# TPaD_Tablet_v1.net
KiCad netlist of a schematic drawn in EAGLE
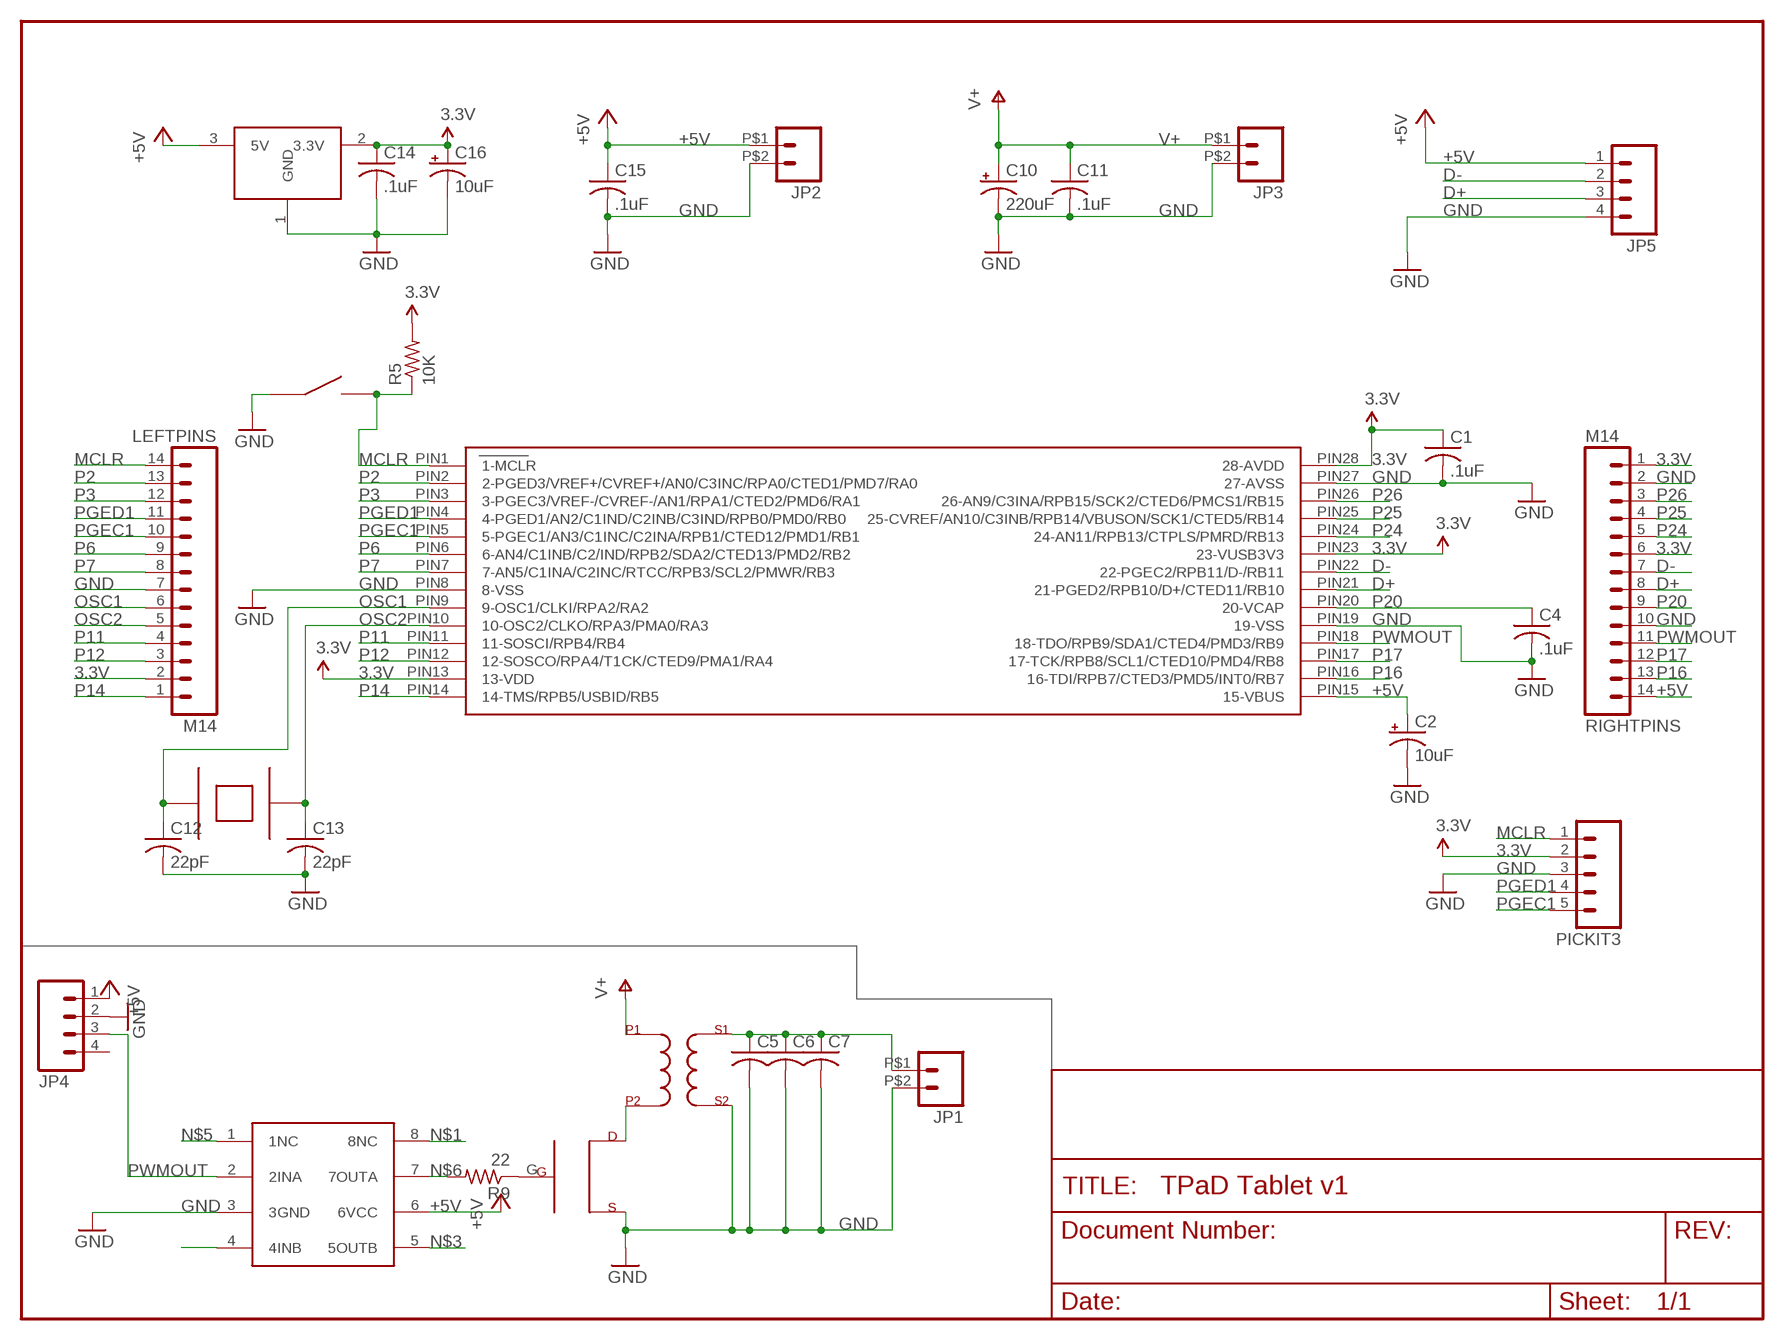
[diagram p0: schematic, sheet 1]

(export (version "E")
  (design (tool "Eeschema 10.0.6"))
  (components
    (comp (ref "C1")
      (value ".1uF")
      (footprint "eagle-import:C050-035X075")
      (libsource (lib "eagle-import") (part "C-US050-035X075"))
    )
    (comp (ref "C2")
      (value "10uF")
      (footprint "eagle-import:E2-5")
      (libsource (lib "eagle-import") (part "CPOL-USE2-5"))
    )
    (comp (ref "C4")
      (value ".1uF")
      (footprint "eagle-import:C050-035X075")
      (libsource (lib "eagle-import") (part "C-US050-035X075"))
    )
    (comp (ref "C5")
      (value "C-US050-035X075")
      (footprint "eagle-import:C050-035X075")
      (libsource (lib "eagle-import") (part "C-US050-035X075"))
    )
    (comp (ref "C6")
      (value "C-US050-035X075")
      (footprint "eagle-import:C050-035X075")
      (libsource (lib "eagle-import") (part "C-US050-035X075"))
    )
    (comp (ref "C7")
      (value "C-US050-035X075")
      (footprint "eagle-import:C050-035X075")
      (libsource (lib "eagle-import") (part "C-US050-035X075"))
    )
    (comp (ref "C10")
      (value "220uF")
      (footprint "eagle-import:TT2D6")
      (libsource (lib "eagle-import") (part "CPOL-USTT2D6"))
    )
    (comp (ref "C11")
      (value ".1uF")
      (footprint "eagle-import:C050-035X075")
      (libsource (lib "eagle-import") (part "C-US050-035X075"))
    )
    (comp (ref "C12")
      (value "22pF")
      (footprint "eagle-import:C025-024X044")
      (libsource (lib "eagle-import") (part "C-US025-024X044"))
    )
    (comp (ref "C13")
      (value "22pF")
      (footprint "eagle-import:C025-024X044")
      (libsource (lib "eagle-import") (part "C-US025-024X044"))
    )
    (comp (ref "C14")
      (value ".1uF")
      (footprint "eagle-import:C050-035X075")
      (libsource (lib "eagle-import") (part "C-US050-035X075"))
    )
    (comp (ref "C15")
      (value ".1uF")
      (footprint "eagle-import:C050-035X075")
      (libsource (lib "eagle-import") (part "C-US050-035X075"))
    )
    (comp (ref "C16")
      (value "10uF")
      (footprint "eagle-import:E2-5")
      (libsource (lib "eagle-import") (part "CPOL-USE2-5"))
    )
    (comp (ref "JP1")
      (value "M02PTH2")
      (footprint "eagle-import:1X02_BIG")
      (libsource (lib "eagle-import") (part "M02PTH2"))
    )
    (comp (ref "JP2")
      (value "M02PTH2")
      (footprint "eagle-import:1X02_BIG")
      (libsource (lib "eagle-import") (part "M02PTH2"))
    )
    (comp (ref "JP3")
      (value "M02PTH2")
      (footprint "eagle-import:1X02_BIG")
      (libsource (lib "eagle-import") (part "M02PTH2"))
    )
    (comp (ref "JP4")
      (value "M04PTH")
      (footprint "eagle-import:1X04")
      (libsource (lib "eagle-import") (part "M04PTH"))
    )
    (comp (ref "JP5")
      (value "M04PTH")
      (footprint "eagle-import:1X04")
      (libsource (lib "eagle-import") (part "SparkFun-Connectors_M04PTH"))
    )
    (comp (ref "LEFTPINS")
      (value "M14")
      (footprint "eagle-import:1X14")
      (libsource (lib "eagle-import") (part "M14"))
    )
    (comp (ref "PICKIT3")
      (value "M05PTH")
      (footprint "eagle-import:1X05")
      (libsource (lib "eagle-import") (part "M05PTH"))
    )
    (comp (ref "R5")
      (value "10K")
      (footprint "eagle-import:0207_10")
      (libsource (lib "eagle-import") (part "R-US_0207/10"))
    )
    (comp (ref "R9")
      (value "22")
      (footprint "eagle-import:0207_10")
      (libsource (lib "eagle-import") (part "R-US_0207/10"))
    )
    (comp (ref "RIGHTPINS")
      (value "M14")
      (footprint "eagle-import:1X14")
      (libsource (lib "eagle-import") (part "M14"))
    )
    (comp (ref "U$1")
      (value "PIC32MX250F128B")
      (footprint "eagle-import:DIP28-PIC32")
      (libsource (lib "eagle-import") (part "PIC32MX250F128B"))
    )
    (comp (ref "U$3")
      (value "GATEDRIVER")
      (footprint "eagle-import:DIL-08")
      (libsource (lib "eagle-import") (part "GATEDRIVER"))
    )
    (comp (ref "U$4")
      (value "TRANSFORMER")
      (footprint "eagle-import:TRANSFORMER")
      (libsource (lib "eagle-import") (part "TRANSFORMER"))
    )
    (comp (ref "U$5")
      (value "TPAD_IRF520N")
      (footprint "eagle-import:TPAD_TO220")
      (libsource (lib "eagle-import") (part "TPAD_IRF520N"))
    )
    (comp (ref "U$6")
      (value "LD33V")
      (footprint "eagle-import:SOT223")
      (libsource (lib "eagle-import") (part "LD33V"))
    )
    (comp (ref "U$7")
      (value "OSCILLATOR")
      (footprint "eagle-import:OSC")
      (libsource (lib "eagle-import") (part "OSCILLATOR"))
    )
    (comp (ref "U$8")
      (value "SWITCH")
      (footprint "eagle-import:OSC")
      (libsource (lib "eagle-import") (part "SWITCH"))
    )
  )
  (nets
    (net (code "1") (name "+5V") (class "Default")
      (node (ref "C15") (pin "1") (pinfunction "1_1") (pintype "passive"))
      (node (ref "C2") (pin "+") (pinfunction "+_+") (pintype "passive"))
      (node (ref "JP2") (pin "P$1") (pinfunction "1_P$1") (pintype "passive"))
      (node (ref "JP4") (pin "1") (pinfunction "1_1") (pintype "passive"))
      (node (ref "JP5") (pin "1") (pinfunction "1_1") (pintype "passive"))
      (node (ref "RIGHTPINS") (pin "14") (pinfunction "14_14") (pintype "passive"))
      (node (ref "U$1") (pin "PIN15") (pinfunction "15-VBUS_PIN15") (pintype "bidirectional"))
      (node (ref "U$3") (pin "6") (pinfunction "6VCC_6") (pintype "bidirectional"))
      (node (ref "U$6") (pin "3") (pinfunction "5V_3") (pintype "bidirectional"))
    )
    (net (code "2") (name "/D+") (class "Default")
      (node (ref "JP5") (pin "3") (pinfunction "3_3") (pintype "passive"))
      (node (ref "RIGHTPINS") (pin "8") (pinfunction "8_8") (pintype "passive"))
      (node (ref "U$1") (pin "PIN21") (pinfunction "21-PGED2/RPB10/D+/CTED11/RB10_PIN21") (pintype "bidirectional"))
    )
    (net (code "3") (name "/D-") (class "Default")
      (node (ref "JP5") (pin "2") (pinfunction "2_2") (pintype "passive"))
      (node (ref "RIGHTPINS") (pin "7") (pinfunction "7_7") (pintype "passive"))
      (node (ref "U$1") (pin "PIN22") (pinfunction "22-PGEC2/RPB11/D-/RB11_PIN22") (pintype "bidirectional"))
    )
    (net (code "4") (name "/MCLR") (class "Default")
      (node (ref "LEFTPINS") (pin "14") (pinfunction "14_14") (pintype "passive"))
      (node (ref "PICKIT3") (pin "1") (pinfunction "1_1") (pintype "passive"))
      (node (ref "R5") (pin "1") (pinfunction "1_1") (pintype "passive"))
      (node (ref "U$1") (pin "PIN1") (pinfunction "1-MCLR_PIN1") (pintype "bidirectional"))
      (node (ref "U$8") (pin "P$3") (pinfunction "P$2_P$3") (pintype "bidirectional"))
    )
    (net (code "5") (name "/N$1") (class "Default")
      (node (ref "U$3") (pin "8") (pinfunction "8NC_8") (pintype "bidirectional"))
    )
    (net (code "6") (name "/N$3") (class "Default")
      (node (ref "U$3") (pin "5") (pinfunction "5OUTB_5") (pintype "bidirectional"))
    )
    (net (code "7") (name "/N$5") (class "Default")
      (node (ref "U$3") (pin "1") (pinfunction "1NC_1") (pintype "bidirectional"))
    )
    (net (code "8") (name "/N$6") (class "Default")
      (node (ref "R9") (pin "2") (pinfunction "2_2") (pintype "passive"))
      (node (ref "U$3") (pin "7") (pinfunction "7OUTA_7") (pintype "bidirectional"))
    )
    (net (code "9") (name "/OSC1") (class "Default")
      (node (ref "C12") (pin "1") (pinfunction "1_1") (pintype "passive"))
      (node (ref "LEFTPINS") (pin "6") (pinfunction "6_6") (pintype "passive"))
      (node (ref "U$1") (pin "PIN9") (pinfunction "9-OSC1/CLKI/RPA2/RA2_PIN9") (pintype "bidirectional"))
      (node (ref "U$7") (pin "P$3") (pinfunction "P$2_P$3") (pintype "bidirectional"))
    )
    (net (code "10") (name "/OSC2") (class "Default")
      (node (ref "C13") (pin "1") (pinfunction "1_1") (pintype "passive"))
      (node (ref "LEFTPINS") (pin "5") (pinfunction "5_5") (pintype "passive"))
      (node (ref "U$1") (pin "PIN10") (pinfunction "10-OSC2/CLKO/RPA3/PMA0/RA3_PIN10") (pintype "bidirectional"))
      (node (ref "U$7") (pin "P$1") (pinfunction "P$1_P$1") (pintype "bidirectional"))
    )
    (net (code "11") (name "/P2") (class "Default")
      (node (ref "LEFTPINS") (pin "13") (pinfunction "13_13") (pintype "passive"))
      (node (ref "U$1") (pin "PIN2") (pinfunction "2-PGED3/VREF+/CVREF+/AN0/C3INC/RPA0/CTED1/PMD7/RA0_PIN2") (pintype "bidirectional"))
    )
    (net (code "12") (name "/P3") (class "Default")
      (node (ref "LEFTPINS") (pin "12") (pinfunction "12_12") (pintype "passive"))
      (node (ref "U$1") (pin "PIN3") (pinfunction "3-PGEC3/VREF-/CVREF-/AN1/RPA1/CTED2/PMD6/RA1_PIN3") (pintype "bidirectional"))
    )
    (net (code "13") (name "/P6") (class "Default")
      (node (ref "LEFTPINS") (pin "9") (pinfunction "9_9") (pintype "passive"))
      (node (ref "U$1") (pin "PIN6") (pinfunction "6-AN4/C1INB/C2/IND/RPB2/SDA2/CTED13/PMD2/RB2_PIN6") (pintype "bidirectional"))
    )
    (net (code "14") (name "/P7") (class "Default")
      (node (ref "LEFTPINS") (pin "8") (pinfunction "8_8") (pintype "passive"))
      (node (ref "U$1") (pin "PIN7") (pinfunction "7-AN5/C1INA/C2INC/RTCC/RPB3/SCL2/PMWR/RB3_PIN7") (pintype "bidirectional"))
    )
    (net (code "15") (name "/P11") (class "Default")
      (node (ref "LEFTPINS") (pin "4") (pinfunction "4_4") (pintype "passive"))
      (node (ref "U$1") (pin "PIN11") (pinfunction "11-SOSCI/RPB4/RB4_PIN11") (pintype "bidirectional"))
    )
    (net (code "16") (name "/P12") (class "Default")
      (node (ref "LEFTPINS") (pin "3") (pinfunction "3_3") (pintype "passive"))
      (node (ref "U$1") (pin "PIN12") (pinfunction "12-SOSCO/RPA4/T1CK/CTED9/PMA1/RA4_PIN12") (pintype "bidirectional"))
    )
    (net (code "17") (name "/P14") (class "Default")
      (node (ref "LEFTPINS") (pin "1") (pinfunction "1_1") (pintype "passive"))
      (node (ref "U$1") (pin "PIN14") (pinfunction "14-TMS/RPB5/USBID/RB5_PIN14") (pintype "bidirectional"))
    )
    (net (code "18") (name "/P16") (class "Default")
      (node (ref "RIGHTPINS") (pin "13") (pinfunction "13_13") (pintype "passive"))
      (node (ref "U$1") (pin "PIN16") (pinfunction "16-TDI/RPB7/CTED3/PMD5/INT0/RB7_PIN16") (pintype "bidirectional"))
    )
    (net (code "19") (name "/P17") (class "Default")
      (node (ref "RIGHTPINS") (pin "12") (pinfunction "12_12") (pintype "passive"))
      (node (ref "U$1") (pin "PIN17") (pinfunction "17-TCK/RPB8/SCL1/CTED10/PMD4/RB8_PIN17") (pintype "bidirectional"))
    )
    (net (code "20") (name "/P20") (class "Default")
      (node (ref "C4") (pin "1") (pinfunction "1_1") (pintype "passive"))
      (node (ref "RIGHTPINS") (pin "9") (pinfunction "9_9") (pintype "passive"))
      (node (ref "U$1") (pin "PIN20") (pinfunction "20-VCAP_PIN20") (pintype "bidirectional"))
    )
    (net (code "21") (name "/P24") (class "Default")
      (node (ref "RIGHTPINS") (pin "5") (pinfunction "5_5") (pintype "passive"))
      (node (ref "U$1") (pin "PIN24") (pinfunction "24-AN11/RPB13/CTPLS/PMRD/RB13_PIN24") (pintype "bidirectional"))
    )
    (net (code "22") (name "/P25") (class "Default")
      (node (ref "RIGHTPINS") (pin "4") (pinfunction "4_4") (pintype "passive"))
      (node (ref "U$1") (pin "PIN25") (pinfunction "25-CVREF/AN10/C3INB/RPB14/VBUSON/SCK1/CTED5/RB14_PIN25") (pintype "bidirectional"))
    )
    (net (code "23") (name "/P26") (class "Default")
      (node (ref "RIGHTPINS") (pin "3") (pinfunction "3_3") (pintype "passive"))
      (node (ref "U$1") (pin "PIN26") (pinfunction "26-AN9/C3INA/RPB15/SCK2/CTED6/PMCS1/RB15_PIN26") (pintype "bidirectional"))
    )
    (net (code "24") (name "/PGEC1") (class "Default")
      (node (ref "LEFTPINS") (pin "10") (pinfunction "10_10") (pintype "passive"))
      (node (ref "PICKIT3") (pin "5") (pinfunction "5_5") (pintype "passive"))
      (node (ref "U$1") (pin "PIN5") (pinfunction "5-PGEC1/AN3/C1INC/C2INA/RPB1/CTED12/PMD1/RB1_PIN5") (pintype "bidirectional"))
    )
    (net (code "25") (name "/PGED1") (class "Default")
      (node (ref "LEFTPINS") (pin "11") (pinfunction "11_11") (pintype "passive"))
      (node (ref "PICKIT3") (pin "4") (pinfunction "4_4") (pintype "passive"))
      (node (ref "U$1") (pin "PIN4") (pinfunction "4-PGED1/AN2/C1IND/C2INB/C3IND/RPB0/PMD0/RB0_PIN4") (pintype "bidirectional"))
    )
    (net (code "26") (name "/PWMOUT") (class "Default")
      (node (ref "JP4") (pin "3") (pinfunction "3_3") (pintype "passive"))
      (node (ref "RIGHTPINS") (pin "11") (pinfunction "11_11") (pintype "passive"))
      (node (ref "U$1") (pin "PIN18") (pinfunction "18-TDO/RPB9/SDA1/CTED4/PMD3/RB9_PIN18") (pintype "bidirectional"))
      (node (ref "U$3") (pin "2") (pinfunction "2INA_2") (pintype "bidirectional"))
    )
    (net (code "27") (name "3.3V") (class "Default")
      (node (ref "C1") (pin "1") (pinfunction "1_1") (pintype "passive"))
      (node (ref "C14") (pin "1") (pinfunction "1_1") (pintype "passive"))
      (node (ref "C16") (pin "+") (pinfunction "+_+") (pintype "passive"))
      (node (ref "LEFTPINS") (pin "2") (pinfunction "2_2") (pintype "passive"))
      (node (ref "PICKIT3") (pin "2") (pinfunction "2_2") (pintype "passive"))
      (node (ref "R5") (pin "2") (pinfunction "2_2") (pintype "passive"))
      (node (ref "RIGHTPINS") (pin "1") (pinfunction "1_1") (pintype "passive"))
      (node (ref "RIGHTPINS") (pin "6") (pinfunction "6_6") (pintype "passive"))
      (node (ref "U$1") (pin "PIN13") (pinfunction "13-VDD_PIN13") (pintype "bidirectional"))
      (node (ref "U$1") (pin "PIN23") (pinfunction "23-VUSB3V3_PIN23") (pintype "bidirectional"))
      (node (ref "U$1") (pin "PIN28") (pinfunction "28-AVDD_PIN28") (pintype "bidirectional"))
      (node (ref "U$6") (pin "2") (pinfunction "3.3V_2") (pintype "bidirectional"))
    )
    (net (code "28") (name "GND") (class "Default")
      (node (ref "C1") (pin "2") (pinfunction "2_2") (pintype "passive"))
      (node (ref "C10") (pin "-") (pinfunction "-_-") (pintype "passive"))
      (node (ref "C11") (pin "2") (pinfunction "2_2") (pintype "passive"))
      (node (ref "C12") (pin "2") (pinfunction "2_2") (pintype "passive"))
      (node (ref "C13") (pin "2") (pinfunction "2_2") (pintype "passive"))
      (node (ref "C14") (pin "2") (pinfunction "2_2") (pintype "passive"))
      (node (ref "C15") (pin "2") (pinfunction "2_2") (pintype "passive"))
      (node (ref "C16") (pin "-") (pinfunction "-_-") (pintype "passive"))
      (node (ref "C2") (pin "-") (pinfunction "-_-") (pintype "passive"))
      (node (ref "C4") (pin "2") (pinfunction "2_2") (pintype "passive"))
      (node (ref "C5") (pin "2") (pinfunction "2_2") (pintype "passive"))
      (node (ref "C6") (pin "2") (pinfunction "2_2") (pintype "passive"))
      (node (ref "C7") (pin "2") (pinfunction "2_2") (pintype "passive"))
      (node (ref "JP1") (pin "P$2") (pinfunction "2_P$2") (pintype "passive"))
      (node (ref "JP2") (pin "P$2") (pinfunction "2_P$2") (pintype "passive"))
      (node (ref "JP3") (pin "P$2") (pinfunction "2_P$2") (pintype "passive"))
      (node (ref "JP4") (pin "2") (pinfunction "2_2") (pintype "passive"))
      (node (ref "JP5") (pin "4") (pinfunction "4_4") (pintype "passive"))
      (node (ref "LEFTPINS") (pin "7") (pinfunction "7_7") (pintype "passive"))
      (node (ref "PICKIT3") (pin "3") (pinfunction "3_3") (pintype "passive"))
      (node (ref "RIGHTPINS") (pin "10") (pinfunction "10_10") (pintype "passive"))
      (node (ref "RIGHTPINS") (pin "2") (pinfunction "2_2") (pintype "passive"))
      (node (ref "U$1") (pin "PIN19") (pinfunction "19-VSS_PIN19") (pintype "bidirectional"))
      (node (ref "U$1") (pin "PIN27") (pinfunction "27-AVSS_PIN27") (pintype "bidirectional"))
      (node (ref "U$1") (pin "PIN8") (pinfunction "8-VSS_PIN8") (pintype "bidirectional"))
      (node (ref "U$3") (pin "3") (pinfunction "3GND_3") (pintype "bidirectional"))
      (node (ref "U$4") (pin "S2") (pinfunction "S2_S2") (pintype "bidirectional"))
      (node (ref "U$5") (pin "S") (pinfunction "S_S") (pintype "bidirectional"))
      (node (ref "U$6") (pin "1") (pinfunction "GND_1") (pintype "bidirectional"))
      (node (ref "U$8") (pin "P$1") (pinfunction "P$1_P$1") (pintype "bidirectional"))
    )
    (net (code "29") (name "Net-(JP1-1)") (class "Default")
      (node (ref "C5") (pin "1") (pinfunction "1_1") (pintype "passive"))
      (node (ref "C6") (pin "1") (pinfunction "1_1") (pintype "passive"))
      (node (ref "C7") (pin "1") (pinfunction "1_1") (pintype "passive"))
      (node (ref "JP1") (pin "P$1") (pinfunction "1_P$1") (pintype "passive"))
      (node (ref "U$4") (pin "S1") (pinfunction "S1_S1") (pintype "bidirectional"))
    )
    (net (code "30") (name "Net-(R9-Pad1)") (class "Default")
      (node (ref "R9") (pin "1") (pinfunction "1_1") (pintype "passive"))
      (node (ref "U$5") (pin "G") (pinfunction "G_G") (pintype "bidirectional"))
    )
    (net (code "31") (name "Net-(U$4-PadP2)") (class "Default")
      (node (ref "U$4") (pin "P2") (pinfunction "P2_P2") (pintype "bidirectional"))
      (node (ref "U$5") (pin "D") (pinfunction "D_D") (pintype "bidirectional"))
    )
    (net (code "32") (name "V+") (class "Default")
      (node (ref "C10") (pin "+") (pinfunction "+_+") (pintype "passive"))
      (node (ref "C11") (pin "1") (pinfunction "1_1") (pintype "passive"))
      (node (ref "JP3") (pin "P$1") (pinfunction "1_P$1") (pintype "passive"))
      (node (ref "U$4") (pin "P1") (pinfunction "P1_P1") (pintype "bidirectional"))
    )
    (net (code "33") (name "unconnected-(JP4-Pad4)") (class "Default")
      (node (ref "JP4") (pin "4") (pinfunction "4_4") (pintype "passive"))
    )
    (net (code "34") (name "unconnected-(U$3-4INB-Pad4)") (class "Default")
      (node (ref "U$3") (pin "4") (pinfunction "4INB_4") (pintype "bidirectional"))
    )
  )
)
